# MAZ000166_-_Diagrama_el_ctrico.net
KiCad netlist of a schematic drawn in Altium Designer
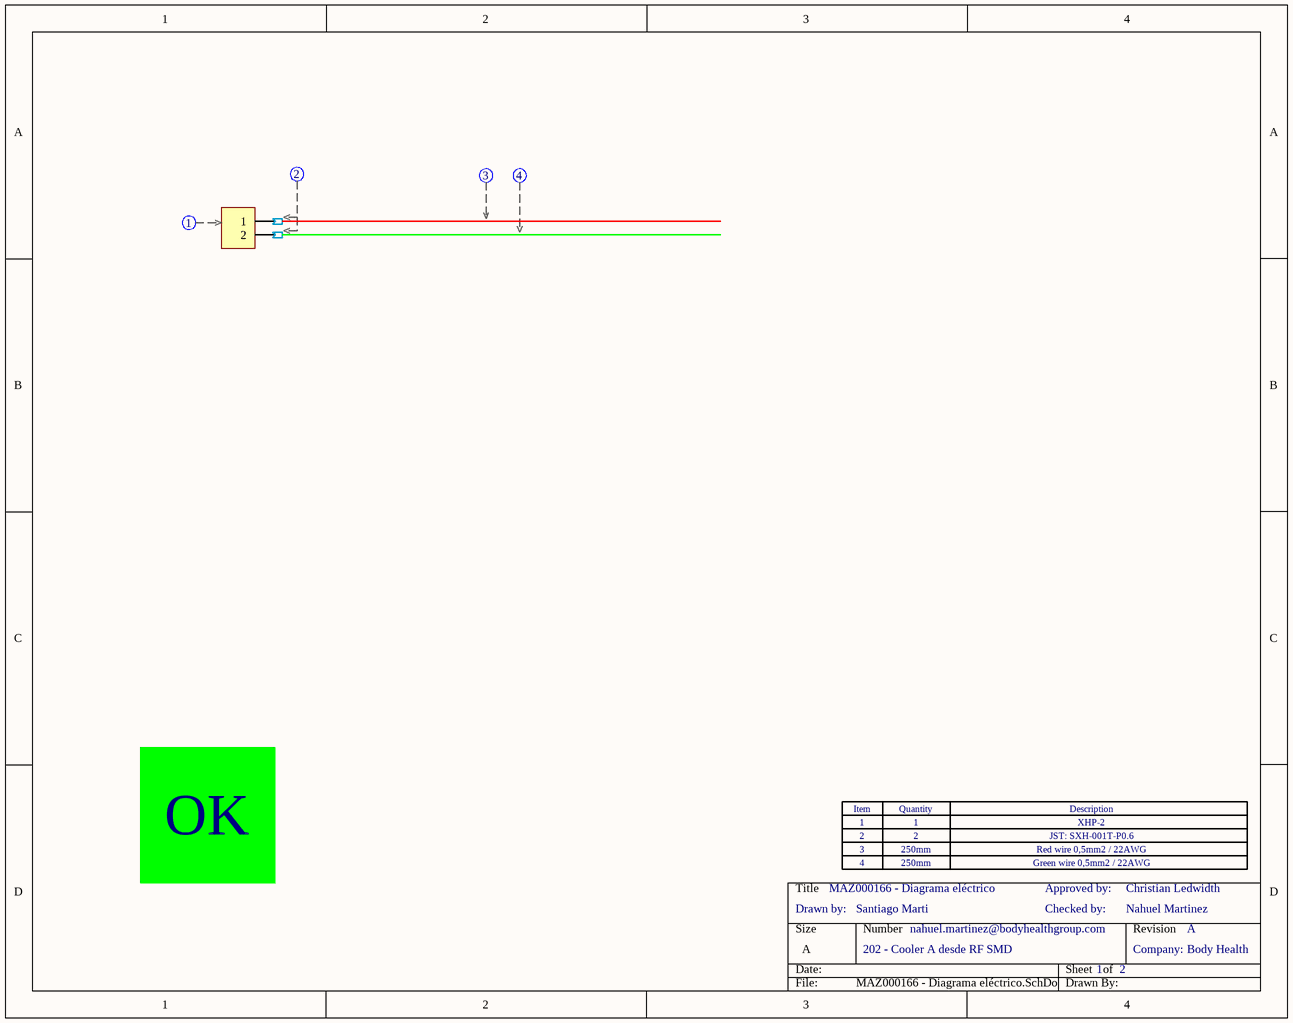
[diagram p0: MAZ000166 - Diagrama eléctrico.SchDoc]

(export (version "E")
  (design (tool "Eeschema 10.0.6"))
  (components
    (comp (ref "Con1")
      (value "XHP-2")
      (description "CONN HOUSING 2.5MM 2POS")
      (libsource (lib "LibreriaParaPlanos") (part "XHP-2"))
    )
    (comp (ref "Soc1")
      (value "sock_XHP_SXH-002T-P0.6")
      (description "CONN SOCKET 26-30AWG CRIMP TIN")
      (libsource (lib "LibreriaParaPlanos") (part "sock_XHP_SXH-002T-P0.6"))
    )
    (comp (ref "Soc2")
      (value "sock_XHP_SXH-002T-P0.6")
      (description "CONN SOCKET 26-30AWG CRIMP TIN")
      (libsource (lib "LibreriaParaPlanos") (part "sock_XHP_SXH-002T-P0.6"))
    )
    (comp (ref "Soc4")
      (value "sock_XHP_SXH-002T-P0.6")
      (description "CONN SOCKET 26-30AWG CRIMP TIN")
      (libsource (lib "LibreriaParaPlanos") (part "sock_XHP_SXH-002T-P0.6"))
    )
    (comp (ref "Zoc1")
      (value "Zócalo_Header")
      (description "Header para el zócalo de referencias")
      (libsource (lib "LibreriaParaPlanos") (part "Zócalo_Header"))
    )
    (comp (ref "Zoc2")
      (value "Zócalo_Item")
      (description "Ítem para el zócalo de referencias")
      (libsource (lib "LibreriaParaPlanos") (part "Zócalo_Item"))
    )
    (comp (ref "Zoc3")
      (value "Zócalo_Item")
      (description "Ítem para el zócalo de referencias")
      (libsource (lib "LibreriaParaPlanos") (part "Zócalo_Item"))
    )
    (comp (ref "Zoc4")
      (value "Zócalo_Item")
      (description "Ítem para el zócalo de referencias")
      (libsource (lib "LibreriaParaPlanos") (part "Zócalo_Item"))
    )
    (comp (ref "Zoc5")
      (value "Zócalo_Item")
      (description "Ítem para el zócalo de referencias")
      (libsource (lib "LibreriaParaPlanos") (part "Zócalo_Item"))
    )
  )
  (nets
    (net (code "1") (name "Net-(Con1-Pad1)") (class "Default")
      (node (ref "Con1") (pin "1") (pinfunction "1_1") (pintype "passive"))
      (node (ref "Soc1") (pin "0") (pinfunction "0_0") (pintype "passive"))
    )
    (net (code "2") (name "Net-(Con1-Pad2)") (class "Default")
      (node (ref "Con1") (pin "2") (pinfunction "2_2") (pintype "passive"))
      (node (ref "Soc2") (pin "0") (pinfunction "0_0") (pintype "passive"))
    )
    (net (code "3") (name "unconnected-(Soc1-Pad1)") (class "Default")
      (node (ref "Soc1") (pin "1") (pinfunction "1_1") (pintype "passive"))
    )
    (net (code "4") (name "unconnected-(Soc2-Pad1)") (class "Default")
      (node (ref "Soc2") (pin "1") (pinfunction "1_1") (pintype "passive"))
    )
  )
)
